# MSU_and_periphery.net
KiCad netlist of a schematic drawn in Altium Designer
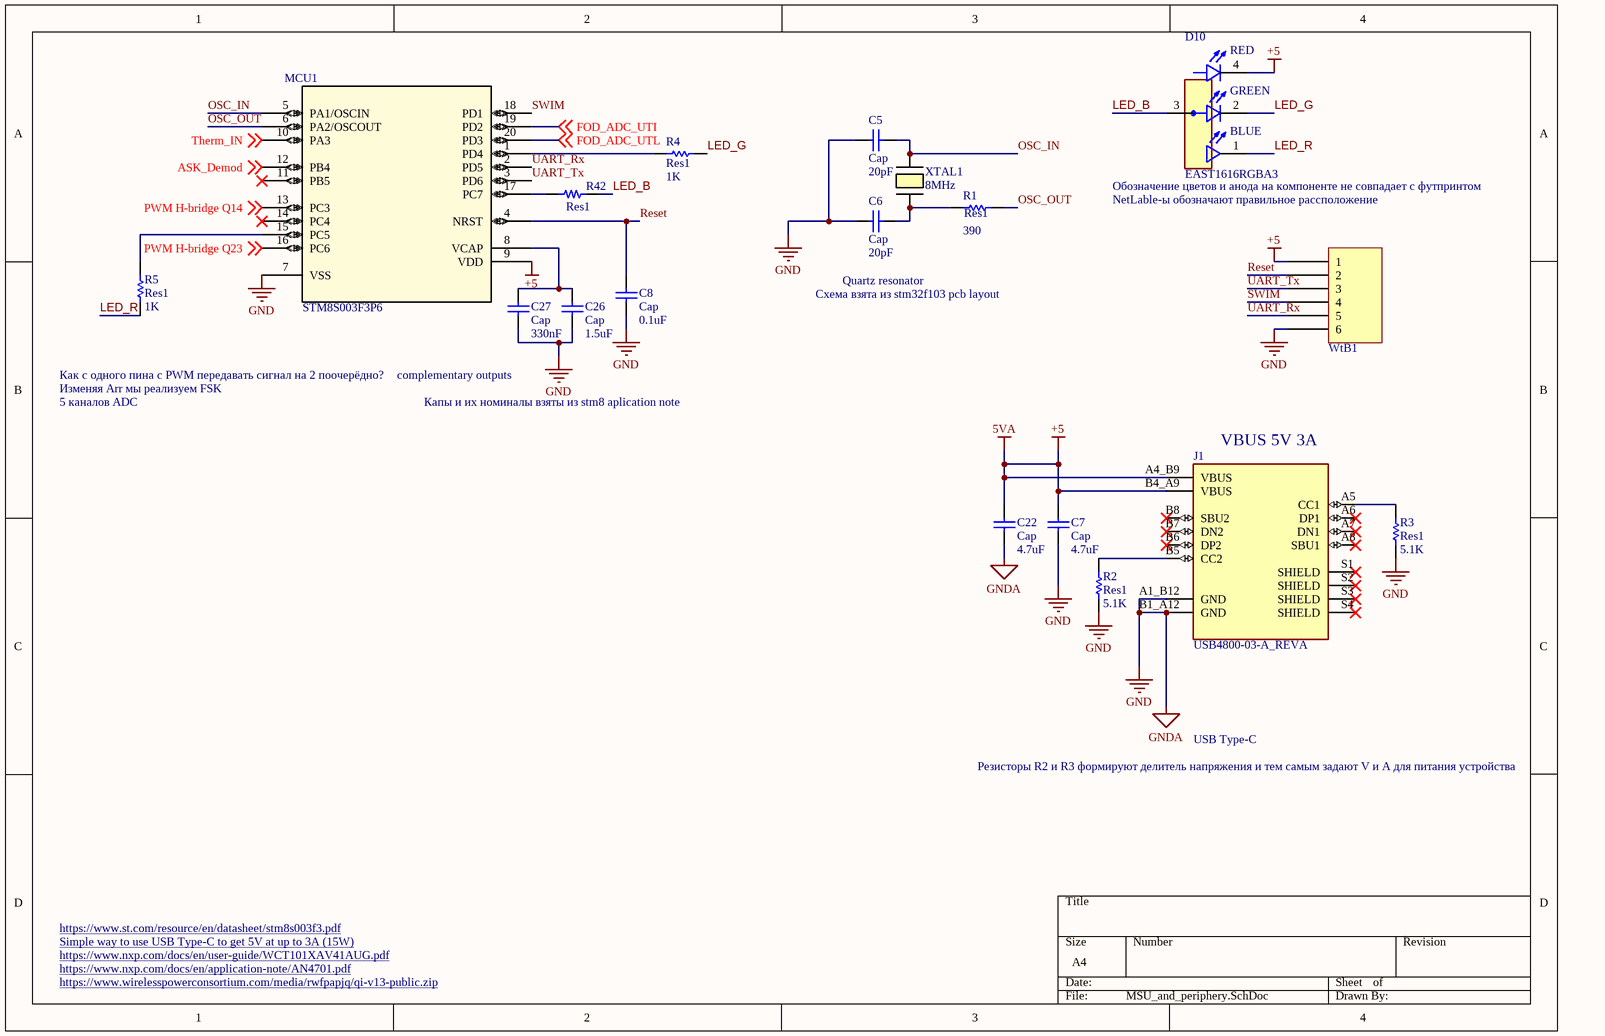
[diagram p0: MSU_and_periphery.SchDoc]

(export (version "E")
  (design (tool "Eeschema 10.0.6"))
  (components
    (comp (ref "C5")
      (value "Cap")
      (footprint "CAP 0402_1005")
      (description "Capacitor")
      (fields (field (name "ALTIUM_VALUE") "20pF") (field (name "PUBLISHER") "Altium Limited"))
      (libsource (lib "Miscellaneous Devices") (part "Cap"))
    )
    (comp (ref "C6")
      (value "Cap")
      (footprint "CAP 0402_1005")
      (description "Capacitor")
      (fields (field (name "ALTIUM_VALUE") "20pF") (field (name "PUBLISHER") "Altium Limited"))
      (libsource (lib "Miscellaneous Devices") (part "Cap"))
    )
    (comp (ref "C7")
      (value "Cap")
      (footprint "CAP 0402_1005")
      (description "Capacitor")
      (fields (field (name "ALTIUM_VALUE") "4.7uF") (field (name "PUBLISHER") "Altium Limited"))
      (libsource (lib "Miscellaneous Devices") (part "Cap"))
    )
    (comp (ref "C8")
      (value "Cap")
      (footprint "CAP 0402_1005")
      (description "Capacitor")
      (fields (field (name "ALTIUM_VALUE") "0.1uF") (field (name "PUBLISHER") "Altium Limited"))
      (libsource (lib "Miscellaneous Devices") (part "Cap"))
    )
    (comp (ref "C22")
      (value "Cap")
      (footprint "CAP 0402_1005")
      (description "Capacitor")
      (fields (field (name "ALTIUM_VALUE") "4.7uF") (field (name "PUBLISHER") "Altium Limited"))
      (libsource (lib "Miscellaneous Devices") (part "Cap"))
    )
    (comp (ref "C26")
      (value "Cap")
      (footprint "CAP 0603_1608")
      (description "Capacitor")
      (fields (field (name "ALTIUM_VALUE") "1.5uF") (field (name "PUBLISHER") "Altium Limited"))
      (libsource (lib "Miscellaneous Devices") (part "Cap"))
    )
    (comp (ref "C27")
      (value "Cap")
      (footprint "CAP 0603_1608")
      (description "Capacitor")
      (fields (field (name "ALTIUM_VALUE") "330nF") (field (name "PUBLISHER") "Altium Limited"))
      (libsource (lib "Miscellaneous Devices") (part "Cap"))
    )
    (comp (ref "D10")
      (value "EAST1616RGBA3")
      (footprint "LED_EAST1616RGBA3")
      (fields (field (name "MF") "Everlight Electronics"))
      (libsource (lib "EAST1616RGBA3") (part "EAST1616RGBA3"))
    )
    (comp (ref "J1")
      (value "USB4800-03-A_REVA")
      (footprint "GCT_USB4800-03-A_REVA")
      (fields (field (name "MP") "USB4800-03-A") (field (name "MF") "Global Connector Technology"))
      (libsource (lib "USB4800-03-A_REVA") (part "USB4800-03-A_REVA"))
    )
    (comp (ref "MCU1")
      (value "STM8S003F3P6")
      (footprint "TSSOP20")
      (description "No Description Available")
      (libsource (lib "STM8S003F3P6") (part "STM8S003F3P6"))
    )
    (comp (ref "R1")
      (value "Res1")
      (footprint "RES 0603_1608")
      (description "Resistor")
      (fields (field (name "ALTIUM_VALUE") "390") (field (name "PUBLISHER") "Altium Limited"))
      (libsource (lib "Miscellaneous Devices") (part "Res1"))
    )
    (comp (ref "R2")
      (value "Res1")
      (footprint "RES 0402_1005")
      (description "Resistor")
      (fields (field (name "ALTIUM_VALUE") "5.1K") (field (name "PUBLISHER") "Altium Limited"))
      (libsource (lib "Miscellaneous Devices") (part "Res1"))
    )
    (comp (ref "R3")
      (value "Res1")
      (footprint "RES 0402_1005")
      (description "Resistor")
      (fields (field (name "ALTIUM_VALUE") "5.1K") (field (name "PUBLISHER") "Altium Limited"))
      (libsource (lib "Miscellaneous Devices") (part "Res1"))
    )
    (comp (ref "R4")
      (value "Res1")
      (footprint "RES 0402_1005")
      (description "Resistor")
      (fields (field (name "ALTIUM_VALUE") "1K") (field (name "PUBLISHER") "Altium Limited"))
      (libsource (lib "Miscellaneous Devices") (part "Res1"))
    )
    (comp (ref "R5")
      (value "Res1")
      (footprint "RES 0402_1005")
      (description "Resistor")
      (fields (field (name "ALTIUM_VALUE") "1K") (field (name "PUBLISHER") "Altium Limited"))
      (libsource (lib "Miscellaneous Devices") (part "Res1"))
    )
    (comp (ref "R42")
      (value "Res1")
      (footprint "RES 0402_1005")
      (description "0402 JUMPER ON TAPE AND REEL")
      (fields (field (name "PART NUMBER") "5112") (field (name "MANUFACTURER") "Keystone Electronics"))
      (libsource (lib "Resistors - Surface Mount - 0402") (part "5112"))
    )
    (comp (ref "WtB1")
      (value "~")
      (footprint "6W_connector")
      (description "Wire to board connector 6pin")
      (libsource (lib "WtB_6_connector") (part "WtB_6_connector"))
    )
    (comp (ref "XTAL1")
      (value "8MHz")
      (footprint "NDK NX5032GA")
      (libsource (lib "ECS-80-18-5PX-TR") (part "ECS-80-18-5PX-TR"))
    )
  )
  (nets
    (net (code "1") (name "+5") (class "Default")
      (node (ref "C22") (pin "1") (pinfunction "1_1") (pintype "passive"))
      (node (ref "C7") (pin "1") (pinfunction "1_1") (pintype "passive"))
      (node (ref "D10") (pin "4") (pinfunction "R_C_4") (pintype "passive"))
      (node (ref "J1") (pin "A4_B9") (pinfunction "VBUS_A4_B9") (pintype "power_in"))
      (node (ref "J1") (pin "B4_A9") (pinfunction "VBUS_B4_A9") (pintype "power_in"))
      (node (ref "MCU1") (pin "9") (pinfunction "VDD_9") (pintype "power_in"))
      (node (ref "WtB1") (pin "1") (pinfunction "1_1") (pintype "passive"))
    )
    (net (code "2") (name "/LED_B") (class "Default")
      (node (ref "D10") (pin "3") (pinfunction "A_3") (pintype "passive"))
      (node (ref "R42") (pin "2") (pinfunction "2_2") (pintype "passive"))
    )
    (net (code "3") (name "/LED_G") (class "Default")
      (node (ref "D10") (pin "2") (pinfunction "G_C_2") (pintype "passive"))
      (node (ref "R4") (pin "1") (pinfunction "1_1") (pintype "passive"))
    )
    (net (code "4") (name "/LED_R") (class "Default")
      (node (ref "D10") (pin "1") (pinfunction "B_C_1") (pintype "passive"))
      (node (ref "R5") (pin "1") (pinfunction "1_1") (pintype "passive"))
    )
    (net (code "5") (name "/OSC_IN") (class "Default")
      (node (ref "C5") (pin "1") (pinfunction "1_1") (pintype "passive"))
      (node (ref "MCU1") (pin "5") (pinfunction "PA1/OSCIN_5") (pintype "bidirectional"))
      (node (ref "XTAL1") (pin "1") (pinfunction "4_1") (pintype "passive"))
    )
    (net (code "6") (name "/OSC_OUT") (class "Default")
      (node (ref "MCU1") (pin "6") (pinfunction "PA2/OSCOUT_6") (pintype "bidirectional"))
      (node (ref "R1") (pin "2") (pinfunction "2_2") (pintype "passive"))
    )
    (net (code "7") (name "/Reset") (class "Default")
      (node (ref "C8") (pin "2") (pinfunction "2_2") (pintype "passive"))
      (node (ref "MCU1") (pin "4") (pinfunction "NRST_4") (pintype "bidirectional"))
      (node (ref "WtB1") (pin "2") (pinfunction "2_2") (pintype "passive"))
    )
    (net (code "8") (name "/SWIM") (class "Default")
      (node (ref "MCU1") (pin "18") (pinfunction "PD1_18") (pintype "bidirectional"))
      (node (ref "WtB1") (pin "4") (pinfunction "4_4") (pintype "passive"))
    )
    (net (code "9") (name "/UART_Rx") (class "Default")
      (node (ref "MCU1") (pin "2") (pinfunction "PD5_2") (pintype "bidirectional"))
      (node (ref "WtB1") (pin "5") (pinfunction "5_5") (pintype "passive"))
    )
    (net (code "10") (name "/UART_Tx") (class "Default")
      (node (ref "MCU1") (pin "3") (pinfunction "PD6_3") (pintype "bidirectional"))
      (node (ref "WtB1") (pin "3") (pinfunction "3_3") (pintype "passive"))
    )
    (net (code "11") (name "ASK_Demod") (class "Default")
      (node (ref "MCU1") (pin "12") (pinfunction "PB4_12") (pintype "bidirectional"))
    )
    (net (code "12") (name "FOD_ADC_UTI") (class "Default")
      (node (ref "MCU1") (pin "19") (pinfunction "PD2_19") (pintype "bidirectional"))
    )
    (net (code "13") (name "FOD_ADC_UTL") (class "Default")
      (node (ref "MCU1") (pin "20") (pinfunction "PD3_20") (pintype "bidirectional"))
    )
    (net (code "14") (name "GND") (class "Default")
      (node (ref "C22") (pin "2") (pinfunction "2_2") (pintype "passive"))
      (node (ref "C26") (pin "2") (pinfunction "2_2") (pintype "passive"))
      (node (ref "C27") (pin "1") (pinfunction "1_1") (pintype "passive"))
      (node (ref "C5") (pin "2") (pinfunction "2_2") (pintype "passive"))
      (node (ref "C6") (pin "2") (pinfunction "2_2") (pintype "passive"))
      (node (ref "C7") (pin "2") (pinfunction "2_2") (pintype "passive"))
      (node (ref "C8") (pin "1") (pinfunction "1_1") (pintype "passive"))
      (node (ref "J1") (pin "A1_B12") (pinfunction "GND_A1_B12") (pintype "power_in"))
      (node (ref "J1") (pin "B1_A12") (pinfunction "GND_B1_A12") (pintype "power_in"))
      (node (ref "MCU1") (pin "7") (pinfunction "VSS_7") (pintype "power_in"))
      (node (ref "R2") (pin "2") (pinfunction "2_2") (pintype "passive"))
      (node (ref "R3") (pin "2") (pinfunction "2_2") (pintype "passive"))
      (node (ref "WtB1") (pin "6") (pinfunction "6_6") (pintype "passive"))
    )
    (net (code "15") (name "Net-(C6-Pad1)") (class "Default")
      (node (ref "C6") (pin "1") (pinfunction "1_1") (pintype "passive"))
      (node (ref "R1") (pin "1") (pinfunction "1_1") (pintype "passive"))
      (node (ref "XTAL1") (pin "2") (pinfunction "2_2") (pintype "passive"))
    )
    (net (code "16") (name "Net-(J1-CC1)") (class "Default")
      (node (ref "J1") (pin "A5") (pinfunction "CC1_A5") (pintype "bidirectional"))
      (node (ref "R3") (pin "1") (pinfunction "1_1") (pintype "passive"))
    )
    (net (code "17") (name "Net-(J1-CC2)") (class "Default")
      (node (ref "J1") (pin "B5") (pinfunction "CC2_B5") (pintype "bidirectional"))
      (node (ref "R2") (pin "1") (pinfunction "1_1") (pintype "passive"))
    )
    (net (code "18") (name "Net-(MCU1-PC5)") (class "Default")
      (node (ref "MCU1") (pin "15") (pinfunction "PC5_15") (pintype "bidirectional"))
      (node (ref "R5") (pin "2") (pinfunction "2_2") (pintype "passive"))
    )
    (net (code "19") (name "Net-(MCU1-PC7)") (class "Default")
      (node (ref "MCU1") (pin "17") (pinfunction "PC7_17") (pintype "bidirectional"))
      (node (ref "R42") (pin "1") (pinfunction "1_1") (pintype "passive"))
    )
    (net (code "20") (name "Net-(MCU1-PD4)") (class "Default")
      (node (ref "MCU1") (pin "1") (pinfunction "PD4_1") (pintype "bidirectional"))
      (node (ref "R4") (pin "2") (pinfunction "2_2") (pintype "passive"))
    )
    (net (code "21") (name "Net-(MCU1-VCAP)") (class "Default")
      (node (ref "C26") (pin "1") (pinfunction "1_1") (pintype "passive"))
      (node (ref "C27") (pin "2") (pinfunction "2_2") (pintype "passive"))
      (node (ref "MCU1") (pin "8") (pinfunction "VCAP_8") (pintype "power_in"))
    )
    (net (code "22") (name "PWM H-bridge Q14") (class "Default")
      (node (ref "MCU1") (pin "13") (pinfunction "PC3_13") (pintype "bidirectional"))
    )
    (net (code "23") (name "PWM H-bridge Q23") (class "Default")
      (node (ref "MCU1") (pin "16") (pinfunction "PC6_16") (pintype "bidirectional"))
    )
    (net (code "24") (name "Therm_IN") (class "Default")
      (node (ref "MCU1") (pin "10") (pinfunction "PA3_10") (pintype "bidirectional"))
    )
    (net (code "25") (name "unconnected-(J1-DN1-PadA7)") (class "Default")
      (node (ref "J1") (pin "A7") (pinfunction "DN1_A7") (pintype "bidirectional+no_connect"))
    )
    (net (code "26") (name "unconnected-(J1-DN2-PadB7)") (class "Default")
      (node (ref "J1") (pin "B7") (pinfunction "DN2_B7") (pintype "bidirectional+no_connect"))
    )
    (net (code "27") (name "unconnected-(J1-DP1-PadA6)") (class "Default")
      (node (ref "J1") (pin "A6") (pinfunction "DP1_A6") (pintype "bidirectional+no_connect"))
    )
    (net (code "28") (name "unconnected-(J1-DP2-PadB6)") (class "Default")
      (node (ref "J1") (pin "B6") (pinfunction "DP2_B6") (pintype "bidirectional+no_connect"))
    )
    (net (code "29") (name "unconnected-(J1-SBU1-PadA8)") (class "Default")
      (node (ref "J1") (pin "A8") (pinfunction "SBU1_A8") (pintype "bidirectional+no_connect"))
    )
    (net (code "30") (name "unconnected-(J1-SBU2-PadB8)") (class "Default")
      (node (ref "J1") (pin "B8") (pinfunction "SBU2_B8") (pintype "bidirectional+no_connect"))
    )
    (net (code "31") (name "unconnected-(J1-SHIELD-PadS1)") (class "Default")
      (node (ref "J1") (pin "S1") (pinfunction "SHIELD_S1") (pintype "passive+no_connect"))
    )
    (net (code "32") (name "unconnected-(J1-SHIELD-PadS2)") (class "Default")
      (node (ref "J1") (pin "S2") (pinfunction "SHIELD_S2") (pintype "passive+no_connect"))
    )
    (net (code "33") (name "unconnected-(J1-SHIELD-PadS3)") (class "Default")
      (node (ref "J1") (pin "S3") (pinfunction "SHIELD_S3") (pintype "passive+no_connect"))
    )
    (net (code "34") (name "unconnected-(J1-SHIELD-PadS4)") (class "Default")
      (node (ref "J1") (pin "S4") (pinfunction "SHIELD_S4") (pintype "passive+no_connect"))
    )
    (net (code "35") (name "unconnected-(MCU1-PB5-Pad11)") (class "Default")
      (node (ref "MCU1") (pin "11") (pinfunction "PB5_11") (pintype "bidirectional+no_connect"))
    )
    (net (code "36") (name "unconnected-(MCU1-PC4-Pad14)") (class "Default")
      (node (ref "MCU1") (pin "14") (pinfunction "PC4_14") (pintype "bidirectional+no_connect"))
    )
  )
)
